# ups.net
KiCad netlist of a schematic drawn in Altium Designer
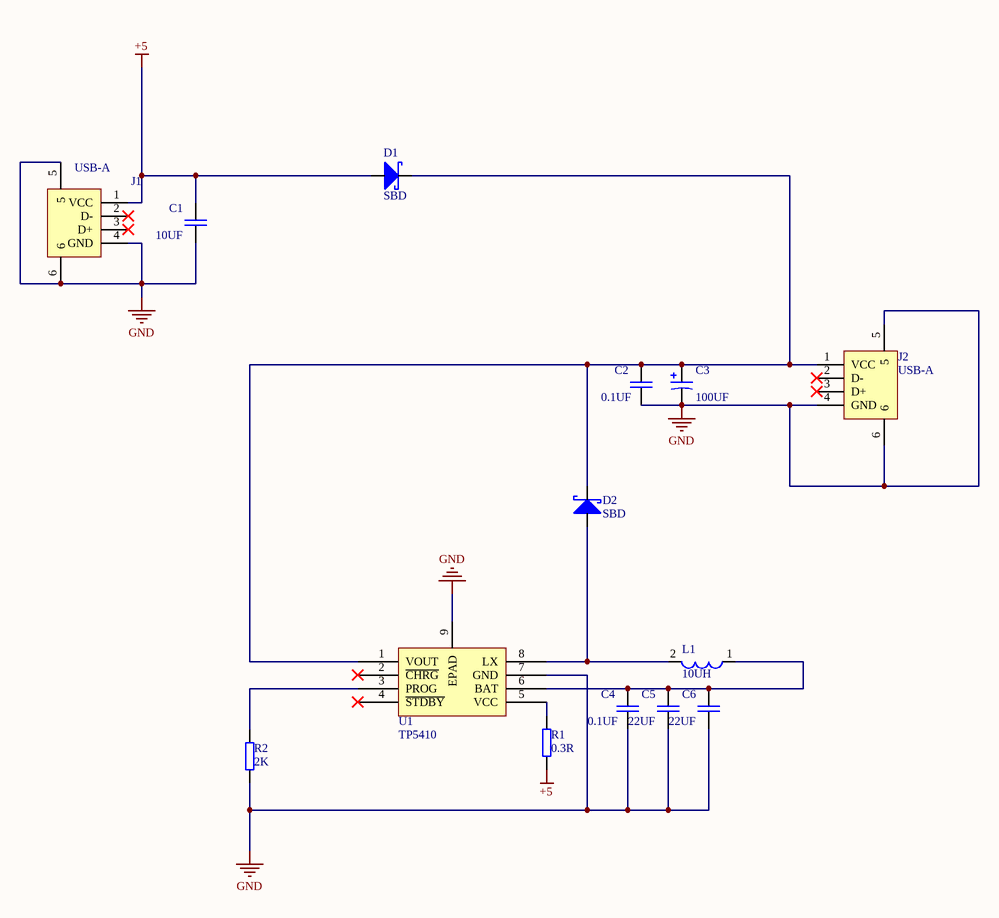
[diagram p0: ups.SchDoc]

(export (version "E")
  (design (tool "Eeschema 10.0.6"))
  (components
    (comp (ref "C1")
      (value "10UF")
      (footprint "1206")
      (description "Capacitor")
      (libsource (lib "SpencerLib") (part "CAP"))
    )
    (comp (ref "C2")
      (value "0.1UF")
      (footprint "0805")
      (description "Capacitor")
      (libsource (lib "SpencerLib") (part "CAP"))
    )
    (comp (ref "C3")
      (value "100UF")
      (footprint "CAP-SMD-3.5X2.8")
      (libsource (lib "SpencerLib") (part "CAP-ELC"))
    )
    (comp (ref "C4")
      (value "0.1UF")
      (footprint "0805")
      (description "Capacitor")
      (libsource (lib "SpencerLib") (part "CAP"))
    )
    (comp (ref "C5")
      (value "22UF")
      (footprint "1206")
      (description "Capacitor")
      (libsource (lib "SpencerLib") (part "CAP"))
    )
    (comp (ref "C6")
      (value "22UF")
      (footprint "1206")
      (description "Capacitor")
      (libsource (lib "SpencerLib") (part "CAP"))
    )
    (comp (ref "D1")
      (value "SBD")
      (footprint "SMA")
      (description "SchottkyBarrierDiode")
      (libsource (lib "SpencerLib") (part "SBD"))
    )
    (comp (ref "D2")
      (value "SBD")
      (footprint "SMA")
      (description "SchottkyBarrierDiode")
      (libsource (lib "SpencerLib") (part "SBD"))
    )
    (comp (ref "J1")
      (value "USB-A")
      (footprint "USB-A-MALE-DD")
      (libsource (lib "SpencerLib") (part "USB-A"))
    )
    (comp (ref "J2") (value "USB-A") (footprint "USB-A-FEMALE-DD") (libsource (lib "") (part "USB-A_1")))
    (comp (ref "L1")
      (value "10UH")
      (footprint "IND-0630")
      (description "Inductor")
      (libsource (lib "SpencerLib") (part "IND"))
    )
    (comp (ref "R1")
      (value "0.3R")
      (footprint "1210")
      (description "Resistor")
      (libsource (lib "SpencerLib") (part "RES"))
    )
    (comp (ref "R2")
      (value "2K")
      (footprint "0603")
      (description "Resistor")
      (libsource (lib "") (part "RES_1"))
    )
    (comp (ref "U1") (value "TP5410") (footprint "ESOP-8") (libsource (lib "SpencerLib") (part "TP5400")))
  )
  (nets
    (net (code "1") (name "+5") (class "Default")
      (node (ref "C1") (pin "1") (pinfunction "1_1") (pintype "passive"))
      (node (ref "D1") (pin "2") (pinfunction "2_2") (pintype "passive"))
      (node (ref "J1") (pin "1") (pinfunction "VCC_1") (pintype "passive"))
      (node (ref "R1") (pin "2") (pinfunction "2_2") (pintype "passive"))
    )
    (net (code "2") (name "GND") (class "Default")
      (node (ref "C1") (pin "2") (pinfunction "2_2") (pintype "passive"))
      (node (ref "C2") (pin "2") (pinfunction "2_2") (pintype "passive"))
      (node (ref "C3") (pin "2") (pinfunction "2_2") (pintype "passive"))
      (node (ref "C4") (pin "2") (pinfunction "2_2") (pintype "passive"))
      (node (ref "C5") (pin "2") (pinfunction "2_2") (pintype "passive"))
      (node (ref "C6") (pin "2") (pinfunction "2_2") (pintype "passive"))
      (node (ref "J1") (pin "4") (pinfunction "GND_4") (pintype "passive"))
      (node (ref "J1") (pin "5") (pinfunction "5_5") (pintype "passive"))
      (node (ref "J1") (pin "6") (pinfunction "6_6") (pintype "passive"))
      (node (ref "J2") (pin "4") (pinfunction "GND_4") (pintype "passive"))
      (node (ref "J2") (pin "5") (pinfunction "5_5") (pintype "passive"))
      (node (ref "J2") (pin "6") (pinfunction "6_6") (pintype "passive"))
      (node (ref "R2") (pin "1") (pinfunction "1_1") (pintype "passive"))
      (node (ref "U1") (pin "7") (pinfunction "GND_7") (pintype "passive"))
      (node (ref "U1") (pin "9") (pinfunction "EPAD_9") (pintype "passive"))
    )
    (net (code "3") (name "Net-(J2-VCC)") (class "Default")
      (node (ref "C2") (pin "1") (pinfunction "1_1") (pintype "passive"))
      (node (ref "C3") (pin "1") (pinfunction "1_1") (pintype "passive"))
      (node (ref "D1") (pin "1") (pinfunction "1_1") (pintype "passive"))
      (node (ref "D2") (pin "1") (pinfunction "1_1") (pintype "passive"))
      (node (ref "J2") (pin "1") (pinfunction "VCC_1") (pintype "passive"))
      (node (ref "U1") (pin "1") (pinfunction "VOUT_1") (pintype "passive"))
    )
    (net (code "4") (name "Net-(U1-BAT)") (class "Default")
      (node (ref "C4") (pin "1") (pinfunction "1_1") (pintype "passive"))
      (node (ref "C5") (pin "1") (pinfunction "1_1") (pintype "passive"))
      (node (ref "C6") (pin "1") (pinfunction "1_1") (pintype "passive"))
      (node (ref "L1") (pin "1") (pinfunction "1_1") (pintype "passive"))
      (node (ref "U1") (pin "6") (pinfunction "BAT_6") (pintype "passive"))
    )
    (net (code "5") (name "Net-(U1-LX)") (class "Default")
      (node (ref "D2") (pin "2") (pinfunction "2_2") (pintype "passive"))
      (node (ref "L1") (pin "2") (pinfunction "2_2") (pintype "passive"))
      (node (ref "U1") (pin "8") (pinfunction "LX_8") (pintype "passive"))
    )
    (net (code "6") (name "Net-(U1-PROG)") (class "Default")
      (node (ref "R2") (pin "2") (pinfunction "2_2") (pintype "passive"))
      (node (ref "U1") (pin "3") (pinfunction "PROG_3") (pintype "passive"))
    )
    (net (code "7") (name "Net-(U1-VCC)") (class "Default")
      (node (ref "R1") (pin "1") (pinfunction "1_1") (pintype "passive"))
      (node (ref "U1") (pin "5") (pinfunction "VCC_5") (pintype "passive"))
    )
    (net (code "8") (name "unconnected-(J1-D+-Pad3)") (class "Default")
      (node (ref "J1") (pin "3") (pinfunction "D+_3") (pintype "passive+no_connect"))
    )
    (net (code "9") (name "unconnected-(J1-D--Pad2)") (class "Default")
      (node (ref "J1") (pin "2") (pinfunction "D-_2") (pintype "passive+no_connect"))
    )
    (net (code "10") (name "unconnected-(J2-D+-Pad3)") (class "Default")
      (node (ref "J2") (pin "3") (pinfunction "D+_3") (pintype "passive+no_connect"))
    )
    (net (code "11") (name "unconnected-(J2-D--Pad2)") (class "Default")
      (node (ref "J2") (pin "2") (pinfunction "D-_2") (pintype "passive+no_connect"))
    )
    (net (code "12") (name "unconnected-(U1-~{CHRG}-Pad2)") (class "Default")
      (node (ref "U1") (pin "2") (pinfunction "~{CHRG}_2") (pintype "passive+no_connect"))
    )
    (net (code "13") (name "unconnected-(U1-~{STDBY}-Pad4)") (class "Default")
      (node (ref "U1") (pin "4") (pinfunction "~{STDBY}_4") (pintype "passive+no_connect"))
    )
  )
)
